# BreakoutBoardMAX.net
KiCad netlist of a schematic drawn in EAGLE
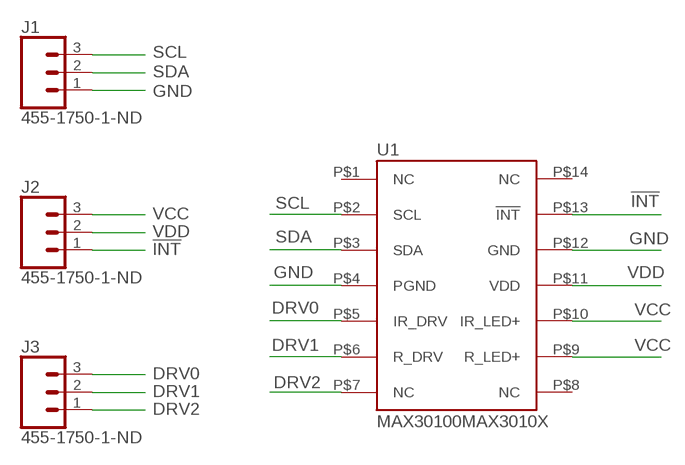
[diagram p0: schematic, sheet 1]

(export (version "E")
  (design (tool "Eeschema 10.0.6"))
  (components
    (comp (ref "J1")
      (value "455-1750-1-ND")
      (footprint "eagle-import:1X03")
      (libsource (lib "eagle-import") (part "CONN_03"))
    )
    (comp (ref "J2")
      (value "455-1750-1-ND")
      (footprint "eagle-import:1X03")
      (libsource (lib "eagle-import") (part "CONN_03"))
    )
    (comp (ref "J3")
      (value "455-1750-1-ND")
      (footprint "eagle-import:1X03")
      (libsource (lib "eagle-import") (part "CONN_03"))
    )
    (comp (ref "U1")
      (value "MAX30100MAX3010X")
      (footprint "eagle-import:MAX_VERSATILE")
      (libsource (lib "eagle-import") (part "MAX30100MAX3010X"))
    )
  )
  (nets
    (net (code "1") (name "/DRV0") (class "Default")
      (node (ref "J3") (pin "3") (pinfunction "3_3") (pintype "passive"))
      (node (ref "U1") (pin "P$5") (pinfunction "IR_DRV_P$5") (pintype "bidirectional"))
    )
    (net (code "2") (name "/DRV1") (class "Default")
      (node (ref "J3") (pin "2") (pinfunction "2_2") (pintype "passive"))
      (node (ref "U1") (pin "P$6") (pinfunction "R_DRV_P$6") (pintype "bidirectional"))
    )
    (net (code "3") (name "/DRV2") (class "Default")
      (node (ref "J3") (pin "1") (pinfunction "1_1") (pintype "passive"))
      (node (ref "U1") (pin "P$7") (pinfunction "NC_P$7") (pintype "bidirectional"))
    )
    (net (code "4") (name "/GND") (class "Default")
      (node (ref "J1") (pin "1") (pinfunction "1_1") (pintype "passive"))
      (node (ref "U1") (pin "P$12") (pinfunction "GND_P$12") (pintype "bidirectional"))
      (node (ref "U1") (pin "P$4") (pinfunction "PGND_P$4") (pintype "bidirectional"))
    )
    (net (code "5") (name "/SCL") (class "Default")
      (node (ref "J1") (pin "3") (pinfunction "3_3") (pintype "passive"))
      (node (ref "U1") (pin "P$2") (pinfunction "SCL_P$2") (pintype "bidirectional"))
    )
    (net (code "6") (name "/SDA") (class "Default")
      (node (ref "J1") (pin "2") (pinfunction "2_2") (pintype "passive"))
      (node (ref "U1") (pin "P$3") (pinfunction "SDA_P$3") (pintype "bidirectional"))
    )
    (net (code "7") (name "/VCC") (class "Default")
      (node (ref "J2") (pin "3") (pinfunction "3_3") (pintype "passive"))
      (node (ref "U1") (pin "P$10") (pinfunction "IR_LED+_P$10") (pintype "bidirectional"))
      (node (ref "U1") (pin "P$9") (pinfunction "R_LED+_P$9") (pintype "bidirectional"))
    )
    (net (code "8") (name "/VDD") (class "Default")
      (node (ref "J2") (pin "2") (pinfunction "2_2") (pintype "passive"))
      (node (ref "U1") (pin "P$11") (pinfunction "VDD_P$11") (pintype "bidirectional"))
    )
    (net (code "9") (name "/~{INT}") (class "Default")
      (node (ref "J2") (pin "1") (pinfunction "1_1") (pintype "passive"))
      (node (ref "U1") (pin "P$13") (pinfunction "~{INT}_P$13") (pintype "bidirectional"))
    )
    (net (code "10") (name "unconnected-(U1-NC-PadP$1)") (class "Default")
      (node (ref "U1") (pin "P$1") (pinfunction "NC_P$1") (pintype "bidirectional"))
    )
    (net (code "11") (name "unconnected-(U1-NC-PadP$8)") (class "Default")
      (node (ref "U1") (pin "P$8") (pinfunction "NC_P$8") (pintype "bidirectional"))
    )
    (net (code "12") (name "unconnected-(U1-NC-PadP$14)") (class "Default")
      (node (ref "U1") (pin "P$14") (pinfunction "NC_P$14") (pintype "bidirectional"))
    )
  )
)
